# 11_-_Power_Input_And_Regulators.net
KiCad netlist of a schematic drawn in Altium Designer
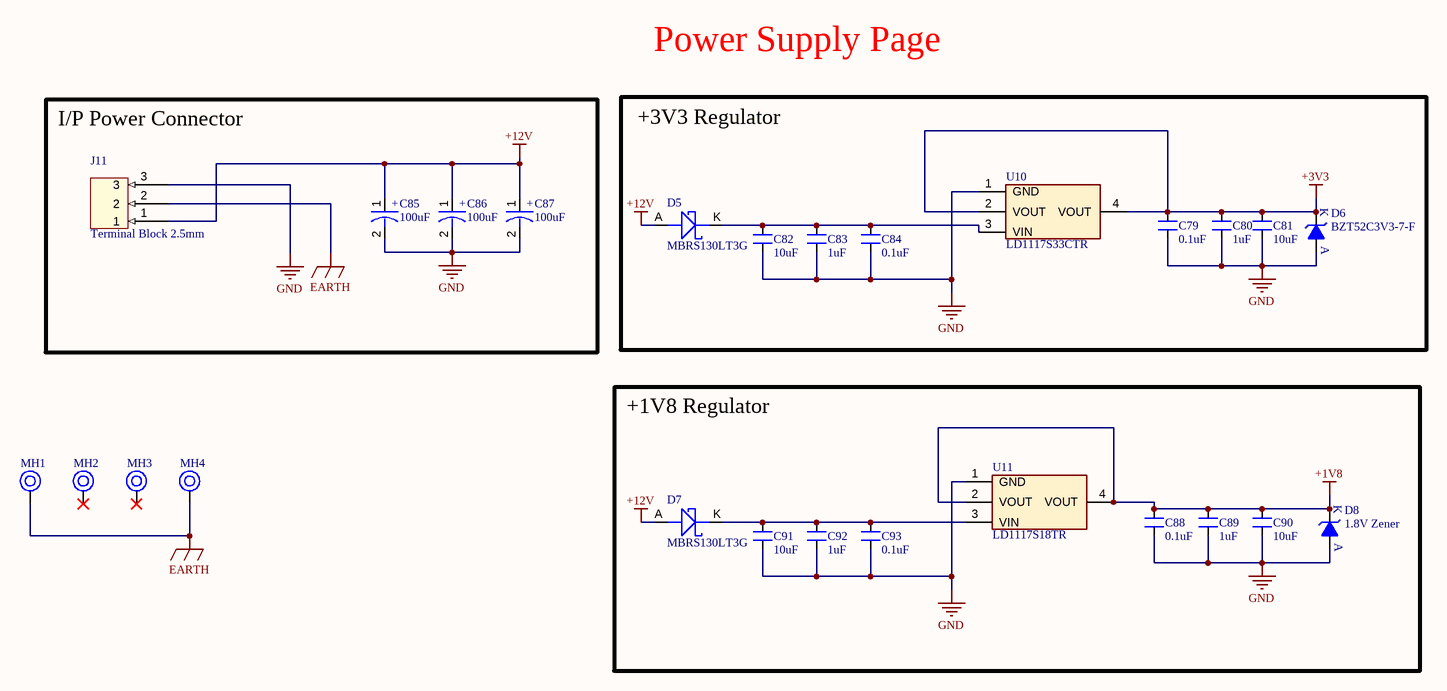
[diagram p0: [11] - Power_Input_And_Regulators.SchDoc]

(export (version "E")
  (design (tool "Eeschema 10.0.6"))
  (components
    (comp (ref "C79")
      (value "0.1uF")
      (footprint "CAP_0805")
      (description "0.1µF ±5% 50V Ceramic Capacitor X7R 0805 (2012 Metric)")
      (fields
        (field (name "MANUFACTURER") "AVX Corporation")
        (field (name "MANUFACTURER PART NUMBER") "08055C104JAT4A")
      )
      (libsource (lib "ESTEEMPCBLIB") (part "CAP_0.1uF-50V-5%-0805"))
    )
    (comp (ref "C80")
      (value "1uF")
      (footprint "CAP_0805")
      (description "1µF ±5% 50V Ceramic Capacitor X7R 0805 (2012 Metric)")
      (fields
        (field (name "MANUFACTURER") "Samsung")
        (field (name "MANUFACTURER PART NUMBER") "CC0805JKX7R9BB105")
      )
      (libsource (lib "ESTEEMPCBLIB") (part "CAP_1uF-50V-5%-0805"))
    )
    (comp (ref "C81")
      (value "10uF")
      (footprint "CAP_1206")
      (description "10µF ±10% 50V Ceramic Capacitor X7R 1206 (3216 Metric)")
      (fields
        (field (name "MANUFACTURER") "KEMET")
        (field (name "MANUFACTURER PART NUMBER") "CL31B106KBHNNNE")
      )
      (libsource (lib "ESTEEMPCBLIB") (part "CAP_10uF-50V-10%-1206"))
    )
    (comp (ref "C82")
      (value "10uF")
      (footprint "CAP_1206")
      (description "10µF ±10% 50V Ceramic Capacitor X7R 1206 (3216 Metric)")
      (fields
        (field (name "MANUFACTURER") "KEMET")
        (field (name "MANUFACTURER PART NUMBER") "CL31B106KBHNNNE")
      )
      (libsource (lib "ESTEEMPCBLIB") (part "CAP_10uF-50V-10%-1206"))
    )
    (comp (ref "C83")
      (value "1uF")
      (footprint "CAP_0805")
      (description "1µF ±5% 50V Ceramic Capacitor X7R 0805 (2012 Metric)")
      (fields
        (field (name "MANUFACTURER") "Samsung")
        (field (name "MANUFACTURER PART NUMBER") "CC0805JKX7R9BB105")
      )
      (libsource (lib "ESTEEMPCBLIB") (part "CAP_1uF-50V-5%-0805"))
    )
    (comp (ref "C84")
      (value "0.1uF")
      (footprint "CAP_0805")
      (description "0.1µF ±5% 50V Ceramic Capacitor X7R 0805 (2012 Metric)")
      (fields
        (field (name "MANUFACTURER") "AVX Corporation")
        (field (name "MANUFACTURER PART NUMBER") "08055C104JAT4A")
      )
      (libsource (lib "ESTEEMPCBLIB") (part "CAP_0.1uF-50V-5%-0805"))
    )
    (comp (ref "C85")
      (value "100uF")
      (footprint "ACAP_P305_D393_H393_RAD")
      (description "100µF 50V Aluminum Polymer Capacitor Radial, Can - SMD 28mOhm 4000 Hrs @ 125°C")
      (fields
        (field (name "MANUFACTURER") "Nichicon")
        (field (name "MANUFACTURER PART NUMBER") "GYA1H101MCQ1GS")
      )
      (libsource (lib "ESTEEMPCBLIB") (part "CAP-P_100uF-50V-20%-RAD"))
    )
    (comp (ref "C86")
      (value "100uF")
      (footprint "ACAP_P305_D393_H393_RAD")
      (description "100µF 50V Aluminum Polymer Capacitor Radial, Can - SMD 28mOhm 4000 Hrs @ 125°C")
      (fields
        (field (name "MANUFACTURER") "Nichicon")
        (field (name "MANUFACTURER PART NUMBER") "GYA1H101MCQ1GS")
      )
      (libsource (lib "ESTEEMPCBLIB") (part "CAP-P_100uF-50V-20%-RAD"))
    )
    (comp (ref "C87")
      (value "100uF")
      (footprint "ACAP_P305_D393_H393_RAD")
      (description "100µF 50V Aluminum Polymer Capacitor Radial, Can - SMD 28mOhm 4000 Hrs @ 125°C")
      (fields
        (field (name "MANUFACTURER") "Nichicon")
        (field (name "MANUFACTURER PART NUMBER") "GYA1H101MCQ1GS")
      )
      (libsource (lib "ESTEEMPCBLIB") (part "CAP-P_100uF-50V-20%-RAD"))
    )
    (comp (ref "C88")
      (value "0.1uF")
      (footprint "CAP_0805")
      (description "0.1µF ±5% 50V Ceramic Capacitor X7R 0805 (2012 Metric)")
      (fields
        (field (name "MANUFACTURER") "AVX Corporation")
        (field (name "MANUFACTURER PART NUMBER") "08055C104JAT4A")
      )
      (libsource (lib "ESTEEMPCBLIB") (part "CAP_0.1uF-50V-5%-0805"))
    )
    (comp (ref "C89")
      (value "1uF")
      (footprint "CAP_0805")
      (description "1µF ±5% 50V Ceramic Capacitor X7R 0805 (2012 Metric)")
      (fields
        (field (name "MANUFACTURER") "Samsung")
        (field (name "MANUFACTURER PART NUMBER") "CC0805JKX7R9BB105")
      )
      (libsource (lib "ESTEEMPCBLIB") (part "CAP_1uF-50V-5%-0805"))
    )
    (comp (ref "C90")
      (value "10uF")
      (footprint "CAP_1206")
      (description "10µF ±10% 50V Ceramic Capacitor X7R 1206 (3216 Metric)")
      (fields
        (field (name "MANUFACTURER") "KEMET")
        (field (name "MANUFACTURER PART NUMBER") "CL31B106KBHNNNE")
      )
      (libsource (lib "ESTEEMPCBLIB") (part "CAP_10uF-50V-10%-1206"))
    )
    (comp (ref "C91")
      (value "10uF")
      (footprint "CAP_1206")
      (description "10µF ±10% 50V Ceramic Capacitor X7R 1206 (3216 Metric)")
      (fields
        (field (name "MANUFACTURER") "KEMET")
        (field (name "MANUFACTURER PART NUMBER") "CL31B106KBHNNNE")
      )
      (libsource (lib "ESTEEMPCBLIB") (part "CAP_10uF-50V-10%-1206"))
    )
    (comp (ref "C92")
      (value "1uF")
      (footprint "CAP_0805")
      (description "1µF ±5% 50V Ceramic Capacitor X7R 0805 (2012 Metric)")
      (fields
        (field (name "MANUFACTURER") "Samsung")
        (field (name "MANUFACTURER PART NUMBER") "CC0805JKX7R9BB105")
      )
      (libsource (lib "ESTEEMPCBLIB") (part "CAP_1uF-50V-5%-0805"))
    )
    (comp (ref "C93")
      (value "0.1uF")
      (footprint "CAP_0805")
      (description "0.1µF ±5% 50V Ceramic Capacitor X7R 0805 (2012 Metric)")
      (fields
        (field (name "MANUFACTURER") "AVX Corporation")
        (field (name "MANUFACTURER PART NUMBER") "08055C104JAT4A")
      )
      (libsource (lib "ESTEEMPCBLIB") (part "CAP_0.1uF-50V-5%-0805"))
    )
    (comp (ref "D5")
      (value "MBRS130LT3G")
      (footprint "DIO_SMB_DO-214AA")
      (description "Diode Schottky 30V 2A Surface Mount SMB")
      (fields (field (name "MANUFACTURER") "ON Semiconductor"))
      (libsource (lib "ESTEEMPCBLIB") (part "DIO-S_445mV-30V-2A-SMB"))
    )
    (comp (ref "D6")
      (value "BZT52C3V3-7-F")
      (footprint "DIO_SOD-123")
      (description "Zener Diode 3.3V 500mW ±6% Surface Mount SOD-123")
      (fields (field (name "MANUFACTURER") "Diodes Incorporated"))
      (libsource (lib "ESTEEMPCBLIB") (part "DIO-Z_3.3V-500mW-SOD123"))
    )
    (comp (ref "D7")
      (value "MBRS130LT3G")
      (footprint "DIO_SMB_DO-214AA")
      (description "Diode Schottky 30V 2A Surface Mount SMB")
      (fields (field (name "MANUFACTURER") "ON Semiconductor"))
      (libsource (lib "ESTEEMPCBLIB") (part "DIO-S_445mV-30V-2A-SMB"))
    )
    (comp (ref "D8")
      (value "1.8V Zener")
      (footprint "DIO_DO-213AB_SMD")
      (description "Zener Diode 1.8V 500mW ±5% Surface Mount DO-213AA")
      (libsource (lib "ESTEEMPCBLIB") (part "DIO-Z_1.8V-500mW-DO213AA"))
    )
    (comp (ref "J11")
      (value "Terminal Block 2.5mm")
      (footprint "CON3_100_TB_TH_ST")
      (description "3 Pins, 1 Row 2.54mm Pitch, straight Connector, male")
      (fields
        (field (name "MANUFACTURER PART NUMBER") "1725669")
        (field (name "MANUFACTURER") "Phoenix Contact")
      )
      (libsource (lib "ESTEEMPCBLIB") (part "CON-TB_3X1-100-ST-TH"))
    )
    (comp (ref "MH1")
      (value "Mounting Hole")
      (footprint "MOUNTING")
      (fields (field (name "MANUFACTURER PART NUMBER") "NA"))
      (libsource (lib "ESTEEMPCBLIB") (part "MH_3.5H_6D"))
    )
    (comp (ref "MH2")
      (value "Mounting Hole")
      (footprint "MOUNTING")
      (fields (field (name "MANUFACTURER PART NUMBER") "NA"))
      (libsource (lib "ESTEEMPCBLIB") (part "MH_3.5H_6D"))
    )
    (comp (ref "MH3")
      (value "Mounting Hole")
      (footprint "MOUNTING")
      (fields (field (name "MANUFACTURER PART NUMBER") "NA"))
      (libsource (lib "ESTEEMPCBLIB") (part "MH_3.5H_6D"))
    )
    (comp (ref "MH4")
      (value "Mounting Hole")
      (footprint "MOUNTING")
      (fields (field (name "MANUFACTURER PART NUMBER") "NA"))
      (libsource (lib "ESTEEMPCBLIB") (part "MH_3.5H_6D"))
    )
    (comp (ref "U10")
      (value "LD1117S33CTR")
      (footprint "SOT223_3")
      (description "Linear Voltage Regulator IC 1 Output 800mA SOT-223")
      (fields (field (name "MANUFACTURER") "STMicroelectronics"))
      (libsource (lib "ESTEEMPCBLIB") (part "REG_15V-3.3V-0.9A-12W-SOT223"))
    )
    (comp (ref "U11")
      (value "LD1117S18TR")
      (footprint "SOT223_3")
      (description "LDO Voltage Regulators 1.8V 0.8A Positive")
      (fields (field (name "MANUFACTURER") "STMicroelectronics"))
      (libsource (lib "ESTEEMPCBLIB") (part "REG_15V-1.8V-0.8A-1.4W-SOT223"))
    )
  )
  (nets
    (net (code "1") (name "+1V8") (class "Default")
      (node (ref "C88") (pin "1") (pinfunction "1_1") (pintype "passive"))
      (node (ref "C89") (pin "1") (pinfunction "1_1") (pintype "passive"))
      (node (ref "C90") (pin "1") (pinfunction "1_1") (pintype "passive"))
      (node (ref "D8") (pin "K") (pinfunction "K_K") (pintype "passive"))
      (node (ref "U11") (pin "2") (pinfunction "VOUT_2") (pintype "passive"))
      (node (ref "U11") (pin "4") (pinfunction "VOUT_4") (pintype "passive"))
    )
    (net (code "2") (name "+3V3") (class "Default")
      (node (ref "C79") (pin "1") (pinfunction "1_1") (pintype "passive"))
      (node (ref "C80") (pin "1") (pinfunction "1_1") (pintype "passive"))
      (node (ref "C81") (pin "1") (pinfunction "1_1") (pintype "passive"))
      (node (ref "D6") (pin "K") (pinfunction "K_K") (pintype "passive"))
      (node (ref "U10") (pin "2") (pinfunction "VOUT_2") (pintype "passive"))
      (node (ref "U10") (pin "4") (pinfunction "VOUT_4") (pintype "passive"))
    )
    (net (code "3") (name "+12V") (class "Default")
      (node (ref "C85") (pin "1") (pinfunction "1_1") (pintype "passive"))
      (node (ref "C86") (pin "1") (pinfunction "1_1") (pintype "passive"))
      (node (ref "C87") (pin "1") (pinfunction "1_1") (pintype "passive"))
      (node (ref "D5") (pin "A") (pinfunction "A_A") (pintype "passive"))
      (node (ref "D7") (pin "A") (pinfunction "A_A") (pintype "passive"))
      (node (ref "J11") (pin "1") (pinfunction "1_1") (pintype "input"))
    )
    (net (code "4") (name "EARTH") (class "Default")
      (node (ref "J11") (pin "2") (pinfunction "2_2") (pintype "input"))
      (node (ref "MH1") (pin "1") (pinfunction "1_1") (pintype "passive"))
      (node (ref "MH4") (pin "1") (pinfunction "1_1") (pintype "passive"))
    )
    (net (code "5") (name "GND") (class "Default")
      (node (ref "C79") (pin "2") (pinfunction "2_2") (pintype "passive"))
      (node (ref "C80") (pin "2") (pinfunction "2_2") (pintype "passive"))
      (node (ref "C81") (pin "2") (pinfunction "2_2") (pintype "passive"))
      (node (ref "C82") (pin "1") (pinfunction "1_1") (pintype "passive"))
      (node (ref "C83") (pin "1") (pinfunction "1_1") (pintype "passive"))
      (node (ref "C84") (pin "1") (pinfunction "1_1") (pintype "passive"))
      (node (ref "C85") (pin "2") (pinfunction "2_2") (pintype "passive"))
      (node (ref "C86") (pin "2") (pinfunction "2_2") (pintype "passive"))
      (node (ref "C87") (pin "2") (pinfunction "2_2") (pintype "passive"))
      (node (ref "C88") (pin "2") (pinfunction "2_2") (pintype "passive"))
      (node (ref "C89") (pin "2") (pinfunction "2_2") (pintype "passive"))
      (node (ref "C90") (pin "2") (pinfunction "2_2") (pintype "passive"))
      (node (ref "C91") (pin "1") (pinfunction "1_1") (pintype "passive"))
      (node (ref "C92") (pin "1") (pinfunction "1_1") (pintype "passive"))
      (node (ref "C93") (pin "1") (pinfunction "1_1") (pintype "passive"))
      (node (ref "D6") (pin "A") (pinfunction "A_A") (pintype "passive"))
      (node (ref "D8") (pin "A") (pinfunction "A_A") (pintype "passive"))
      (node (ref "J11") (pin "3") (pinfunction "3_3") (pintype "input"))
      (node (ref "U10") (pin "1") (pinfunction "GND_1") (pintype "passive"))
      (node (ref "U11") (pin "1") (pinfunction "GND_1") (pintype "passive"))
    )
    (net (code "6") (name "Net-(U10-VIN)") (class "Default")
      (node (ref "C82") (pin "2") (pinfunction "2_2") (pintype "passive"))
      (node (ref "C83") (pin "2") (pinfunction "2_2") (pintype "passive"))
      (node (ref "C84") (pin "2") (pinfunction "2_2") (pintype "passive"))
      (node (ref "D5") (pin "K") (pinfunction "K_K") (pintype "passive"))
      (node (ref "U10") (pin "3") (pinfunction "VIN_3") (pintype "passive"))
    )
    (net (code "7") (name "Net-(U11-VIN)") (class "Default")
      (node (ref "C91") (pin "2") (pinfunction "2_2") (pintype "passive"))
      (node (ref "C92") (pin "2") (pinfunction "2_2") (pintype "passive"))
      (node (ref "C93") (pin "2") (pinfunction "2_2") (pintype "passive"))
      (node (ref "D7") (pin "K") (pinfunction "K_K") (pintype "passive"))
      (node (ref "U11") (pin "3") (pinfunction "VIN_3") (pintype "passive"))
    )
    (net (code "8") (name "unconnected-(MH2-Pad1)") (class "Default")
      (node (ref "MH2") (pin "1") (pinfunction "1_1") (pintype "passive+no_connect"))
    )
    (net (code "9") (name "unconnected-(MH3-Pad1)") (class "Default")
      (node (ref "MH3") (pin "1") (pinfunction "1_1") (pintype "passive+no_connect"))
    )
  )
)
